# zero_board.net
KiCad netlist of a schematic drawn in EAGLE
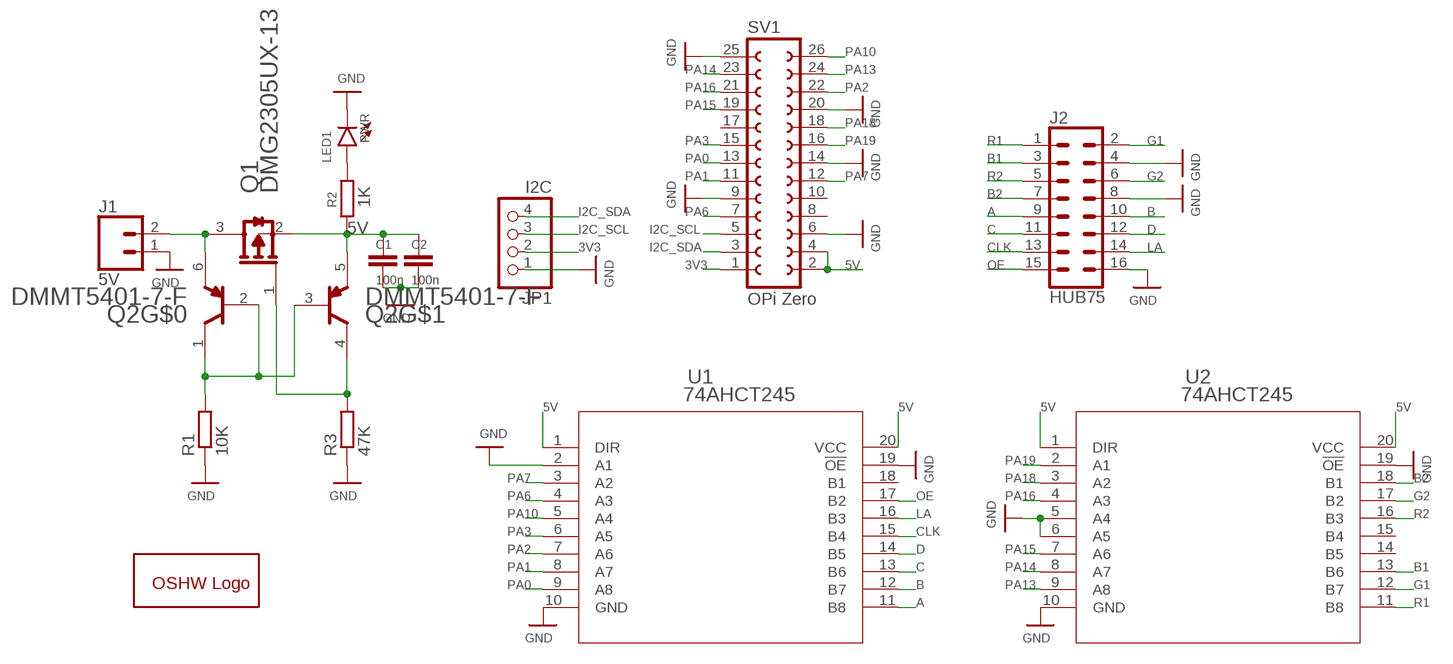
[diagram p0: schematic, sheet 1]

(export (version "E")
  (design (tool "Eeschema 10.0.6"))
  (components
    (comp (ref "C1")
      (value "100n")
      (footprint "eagle-import:C0603")
      (libsource (lib "eagle-import") (part "C-EUC0603"))
    )
    (comp (ref "C2")
      (value "100n")
      (footprint "eagle-import:C0603")
      (libsource (lib "eagle-import") (part "C-EUC0603"))
    )
    (comp (ref "GOLD_ORB_SM1")
      (value "OSHWLOGOLOGO5MM")
      (footprint "eagle-import:OSHW_5MM")
      (libsource (lib "eagle-import") (part "OSHWLOGOLOGO5MM"))
    )
    (comp (ref "J1")
      (value "5V")
      (footprint "eagle-import:SCREWTERMINAL-3.5MM-2")
      (libsource (lib "eagle-import") (part "CONN_023.5MM"))
    )
    (comp (ref "J2")
      (value "HUB75")
      (footprint "eagle-import:2X8-SHROUDED_LOCK")
      (libsource (lib "eagle-import") (part "CONN_08X2_SHROUD"))
    )
    (comp (ref "JP1")
      (value "I2C")
      (footprint "eagle-import:1X04")
      (libsource (lib "eagle-import") (part "PINHD-1X4"))
    )
    (comp (ref "LED1")
      (value "PWR")
      (footprint "eagle-import:CHIP-LED0603")
      (libsource (lib "eagle-import") (part "LEDCHIP-LED0603"))
    )
    (comp (ref "Q1")
      (value "DIODES_INC._DMG2305UX-13DIODES_INC._DMG2305UX-13_0_0")
      (footprint "eagle-import:DIODES_INC._DMG2305UX-13_0")
      (fields
        (field (name "DIGIKEY_PART_NUMBER") "DMG2305UX-13DICT-ND")
        (field (name "MF") "Diodes Inc.")
        (field (name "MOUSER_PART_NUMBER") "621-DMG2305UX-13")
      )
      (libsource (lib "eagle-import") (part "DIODES_INC._DMG2305UX-13DIODES_INC._DMG2305UX-13_0_0"))
    )
    (comp (ref "Q2")
      (value "DIODES_DMMT5401-7-FDIODES_DMMT5401-7-F_0_0")
      (footprint "eagle-import:DIODES_DMMT5401-7-F_0")
      (fields
        (field (name "DIGIKEY_PART_NUMBER") "DMMT5401-FDICT-ND")
        (field (name "MF") "Diodes")
        (field (name "MOUSER_PART_NUMBER") "621-DMMT5401-7-F")
      )
      (libsource (lib "eagle-import") (part "DIODES_DMMT5401-7-FDIODES_DMMT5401-7-F_0_0"))
    )
    (comp (ref "R1")
      (value "10K")
      (footprint "eagle-import:R0402")
      (libsource (lib "eagle-import") (part "R-EU_R0402"))
    )
    (comp (ref "R2")
      (value "1K")
      (footprint "eagle-import:R0603")
      (libsource (lib "eagle-import") (part "resistor_348_R-EU_R0603"))
    )
    (comp (ref "R3")
      (value "47K")
      (footprint "eagle-import:R0402")
      (libsource (lib "eagle-import") (part "R-EU_R0402"))
    )
    (comp (ref "SV1")
      (value "OPi Zero")
      (footprint "eagle-import:FE13-2")
      (libsource (lib "eagle-import") (part "FE13-2"))
    )
    (comp (ref "U1")
      (value "74AHCT245")
      (footprint "eagle-import:PW20")
      (fields
        (field (name "GENERIC_PART_NUMBER") "SN74HCT245")
        (field (name "MANUFACTURER") "Texas Instruments")
        (field (name "MANUFACTURER_PART_NUMBER") "SN74HCT245PWR")
      )
      (libsource (lib "eagle-import") (part "SN74HCT245PWR"))
    )
    (comp (ref "U2")
      (value "74AHCT245")
      (footprint "eagle-import:PW20")
      (fields
        (field (name "GENERIC_PART_NUMBER") "SN74HCT245")
        (field (name "MANUFACTURER") "Texas Instruments")
        (field (name "MANUFACTURER_PART_NUMBER") "SN74HCT245PWR")
      )
      (libsource (lib "eagle-import") (part "SN74HCT245PWR"))
    )
  )
  (nets
    (net (code "1") (name "/3V3") (class "Default")
      (node (ref "JP1") (pin "2") (pinfunction "2_2") (pintype "passive"))
      (node (ref "SV1") (pin "1") (pinfunction "1_1") (pintype "passive"))
    )
    (net (code "2") (name "/5V") (class "Default")
      (node (ref "C1") (pin "1") (pinfunction "1_1") (pintype "passive"))
      (node (ref "C2") (pin "1") (pinfunction "1_1") (pintype "passive"))
      (node (ref "Q1") (pin "2") (pinfunction "S_2") (pintype "passive"))
      (node (ref "Q2") (pin "5") (pinfunction "E2_5") (pintype "passive"))
      (node (ref "R2") (pin "1") (pinfunction "1_1") (pintype "passive"))
      (node (ref "SV1") (pin "2") (pinfunction "2_2") (pintype "passive"))
      (node (ref "SV1") (pin "4") (pinfunction "4_4") (pintype "passive"))
      (node (ref "U1") (pin "1") (pinfunction "DIR_1") (pintype "input"))
      (node (ref "U1") (pin "20") (pinfunction "VCC_20") (pintype "power_in"))
      (node (ref "U2") (pin "1") (pinfunction "DIR_1") (pintype "input"))
      (node (ref "U2") (pin "20") (pinfunction "VCC_20") (pintype "power_in"))
    )
    (net (code "3") (name "/A") (class "Default")
      (node (ref "J2") (pin "9") (pinfunction "9_9") (pintype "passive"))
      (node (ref "U1") (pin "11") (pinfunction "B8_11") (pintype "bidirectional"))
    )
    (net (code "4") (name "/B") (class "Default")
      (node (ref "J2") (pin "10") (pinfunction "10_10") (pintype "passive"))
      (node (ref "U1") (pin "12") (pinfunction "B7_12") (pintype "bidirectional"))
    )
    (net (code "5") (name "/B1") (class "Default")
      (node (ref "J2") (pin "3") (pinfunction "3_3") (pintype "passive"))
      (node (ref "U2") (pin "13") (pinfunction "B6_13") (pintype "bidirectional"))
    )
    (net (code "6") (name "/B2") (class "Default")
      (node (ref "J2") (pin "7") (pinfunction "7_7") (pintype "passive"))
      (node (ref "U2") (pin "18") (pinfunction "B1_18") (pintype "bidirectional"))
    )
    (net (code "7") (name "/C") (class "Default")
      (node (ref "J2") (pin "11") (pinfunction "11_11") (pintype "passive"))
      (node (ref "U1") (pin "13") (pinfunction "B6_13") (pintype "bidirectional"))
    )
    (net (code "8") (name "/CLK") (class "Default")
      (node (ref "J2") (pin "13") (pinfunction "13_13") (pintype "passive"))
      (node (ref "U1") (pin "15") (pinfunction "B4_15") (pintype "bidirectional"))
    )
    (net (code "9") (name "/D") (class "Default")
      (node (ref "J2") (pin "12") (pinfunction "12_12") (pintype "passive"))
      (node (ref "U1") (pin "14") (pinfunction "B5_14") (pintype "bidirectional"))
    )
    (net (code "10") (name "/G1") (class "Default")
      (node (ref "J2") (pin "2") (pinfunction "2_2") (pintype "passive"))
      (node (ref "U2") (pin "12") (pinfunction "B7_12") (pintype "bidirectional"))
    )
    (net (code "11") (name "/G2") (class "Default")
      (node (ref "J2") (pin "6") (pinfunction "6_6") (pintype "passive"))
      (node (ref "U2") (pin "17") (pinfunction "B2_17") (pintype "bidirectional"))
    )
    (net (code "12") (name "/I2C_SCL") (class "Default")
      (node (ref "JP1") (pin "3") (pinfunction "3_3") (pintype "passive"))
      (node (ref "SV1") (pin "5") (pinfunction "5_5") (pintype "passive"))
    )
    (net (code "13") (name "/I2C_SDA") (class "Default")
      (node (ref "JP1") (pin "4") (pinfunction "4_4") (pintype "passive"))
      (node (ref "SV1") (pin "3") (pinfunction "3_3") (pintype "passive"))
    )
    (net (code "14") (name "/LA") (class "Default")
      (node (ref "J2") (pin "14") (pinfunction "14_14") (pintype "passive"))
      (node (ref "U1") (pin "16") (pinfunction "B3_16") (pintype "bidirectional"))
    )
    (net (code "15") (name "/OE") (class "Default")
      (node (ref "J2") (pin "15") (pinfunction "15_15") (pintype "passive"))
      (node (ref "U1") (pin "17") (pinfunction "B2_17") (pintype "bidirectional"))
    )
    (net (code "16") (name "/PA0") (class "Default")
      (node (ref "SV1") (pin "13") (pinfunction "13_13") (pintype "passive"))
      (node (ref "U1") (pin "9") (pinfunction "A8_9") (pintype "bidirectional"))
    )
    (net (code "17") (name "/PA1") (class "Default")
      (node (ref "SV1") (pin "11") (pinfunction "11_11") (pintype "passive"))
      (node (ref "U1") (pin "8") (pinfunction "A7_8") (pintype "bidirectional"))
    )
    (net (code "18") (name "/PA2") (class "Default")
      (node (ref "SV1") (pin "22") (pinfunction "22_22") (pintype "passive"))
      (node (ref "U1") (pin "7") (pinfunction "A6_7") (pintype "bidirectional"))
    )
    (net (code "19") (name "/PA3") (class "Default")
      (node (ref "SV1") (pin "15") (pinfunction "15_15") (pintype "passive"))
      (node (ref "U1") (pin "6") (pinfunction "A5_6") (pintype "bidirectional"))
    )
    (net (code "20") (name "/PA6") (class "Default")
      (node (ref "SV1") (pin "7") (pinfunction "7_7") (pintype "passive"))
      (node (ref "U1") (pin "4") (pinfunction "A3_4") (pintype "bidirectional"))
    )
    (net (code "21") (name "/PA7") (class "Default")
      (node (ref "SV1") (pin "12") (pinfunction "12_12") (pintype "passive"))
      (node (ref "U1") (pin "3") (pinfunction "A2_3") (pintype "bidirectional"))
    )
    (net (code "22") (name "/PA10") (class "Default")
      (node (ref "SV1") (pin "26") (pinfunction "26_26") (pintype "passive"))
      (node (ref "U1") (pin "5") (pinfunction "A4_5") (pintype "bidirectional"))
    )
    (net (code "23") (name "/PA13") (class "Default")
      (node (ref "SV1") (pin "24") (pinfunction "24_24") (pintype "passive"))
      (node (ref "U2") (pin "9") (pinfunction "A8_9") (pintype "bidirectional"))
    )
    (net (code "24") (name "/PA14") (class "Default")
      (node (ref "SV1") (pin "23") (pinfunction "23_23") (pintype "passive"))
      (node (ref "U2") (pin "8") (pinfunction "A7_8") (pintype "bidirectional"))
    )
    (net (code "25") (name "/PA15") (class "Default")
      (node (ref "SV1") (pin "19") (pinfunction "19_19") (pintype "passive"))
      (node (ref "U2") (pin "7") (pinfunction "A6_7") (pintype "bidirectional"))
    )
    (net (code "26") (name "/PA16") (class "Default")
      (node (ref "SV1") (pin "21") (pinfunction "21_21") (pintype "passive"))
      (node (ref "U2") (pin "4") (pinfunction "A3_4") (pintype "bidirectional"))
    )
    (net (code "27") (name "/PA18") (class "Default")
      (node (ref "SV1") (pin "18") (pinfunction "18_18") (pintype "passive"))
      (node (ref "U2") (pin "3") (pinfunction "A2_3") (pintype "bidirectional"))
    )
    (net (code "28") (name "/PA19") (class "Default")
      (node (ref "SV1") (pin "16") (pinfunction "16_16") (pintype "passive"))
      (node (ref "U2") (pin "2") (pinfunction "A1_2") (pintype "bidirectional"))
    )
    (net (code "29") (name "/R1") (class "Default")
      (node (ref "J2") (pin "1") (pinfunction "1_1") (pintype "passive"))
      (node (ref "U2") (pin "11") (pinfunction "B8_11") (pintype "bidirectional"))
    )
    (net (code "30") (name "/R2") (class "Default")
      (node (ref "J2") (pin "5") (pinfunction "5_5") (pintype "passive"))
      (node (ref "U2") (pin "16") (pinfunction "B3_16") (pintype "bidirectional"))
    )
    (net (code "31") (name "GND") (class "Default")
      (node (ref "C1") (pin "2") (pinfunction "2_2") (pintype "passive"))
      (node (ref "C2") (pin "2") (pinfunction "2_2") (pintype "passive"))
      (node (ref "J1") (pin "1") (pinfunction "1_1") (pintype "passive"))
      (node (ref "J2") (pin "16") (pinfunction "16_16") (pintype "passive"))
      (node (ref "J2") (pin "4") (pinfunction "4_4") (pintype "passive"))
      (node (ref "J2") (pin "8") (pinfunction "8_8") (pintype "passive"))
      (node (ref "JP1") (pin "1") (pinfunction "1_1") (pintype "passive"))
      (node (ref "LED1") (pin "C") (pinfunction "C_C") (pintype "passive"))
      (node (ref "R1") (pin "1") (pinfunction "1_1") (pintype "passive"))
      (node (ref "R3") (pin "1") (pinfunction "1_1") (pintype "passive"))
      (node (ref "SV1") (pin "14") (pinfunction "14_14") (pintype "passive"))
      (node (ref "SV1") (pin "20") (pinfunction "20_20") (pintype "passive"))
      (node (ref "SV1") (pin "25") (pinfunction "25_25") (pintype "passive"))
      (node (ref "SV1") (pin "6") (pinfunction "6_6") (pintype "passive"))
      (node (ref "SV1") (pin "9") (pinfunction "9_9") (pintype "passive"))
      (node (ref "U1") (pin "10") (pinfunction "GND_10") (pintype "power_in"))
      (node (ref "U1") (pin "19") (pinfunction "~{OE}_19") (pintype "input"))
      (node (ref "U1") (pin "2") (pinfunction "A1_2") (pintype "bidirectional"))
      (node (ref "U2") (pin "10") (pinfunction "GND_10") (pintype "power_in"))
      (node (ref "U2") (pin "19") (pinfunction "~{OE}_19") (pintype "input"))
      (node (ref "U2") (pin "5") (pinfunction "A4_5") (pintype "bidirectional"))
      (node (ref "U2") (pin "6") (pinfunction "A5_6") (pintype "bidirectional"))
    )
    (net (code "32") (name "Net-(LED1-PadA)") (class "Default")
      (node (ref "LED1") (pin "A") (pinfunction "A_A") (pintype "passive"))
      (node (ref "R2") (pin "2") (pinfunction "2_2") (pintype "passive"))
    )
    (net (code "33") (name "Net-(Q1-D)") (class "Default")
      (node (ref "J1") (pin "2") (pinfunction "2_2") (pintype "passive"))
      (node (ref "Q1") (pin "3") (pinfunction "D_3") (pintype "passive"))
      (node (ref "Q2") (pin "6") (pinfunction "E1_6") (pintype "passive"))
    )
    (net (code "34") (name "Net-(Q1-G)") (class "Default")
      (node (ref "Q1") (pin "1") (pinfunction "G_1") (pintype "passive"))
      (node (ref "Q2") (pin "4") (pinfunction "C2_4") (pintype "passive"))
      (node (ref "R3") (pin "2") (pinfunction "2_2") (pintype "passive"))
    )
    (net (code "35") (name "Net-(Q2A-B1)") (class "Default")
      (node (ref "Q2") (pin "1") (pinfunction "C1_1") (pintype "passive"))
      (node (ref "Q2") (pin "2") (pinfunction "B1_2") (pintype "passive"))
      (node (ref "Q2") (pin "3") (pinfunction "B2_3") (pintype "passive"))
      (node (ref "R1") (pin "2") (pinfunction "2_2") (pintype "passive"))
    )
    (net (code "36") (name "unconnected-(SV1-Pad8)") (class "Default")
      (node (ref "SV1") (pin "8") (pinfunction "8_8") (pintype "passive"))
    )
    (net (code "37") (name "unconnected-(SV1-Pad10)") (class "Default")
      (node (ref "SV1") (pin "10") (pinfunction "10_10") (pintype "passive"))
    )
    (net (code "38") (name "unconnected-(SV1-Pad17)") (class "Default")
      (node (ref "SV1") (pin "17") (pinfunction "17_17") (pintype "passive"))
    )
    (net (code "39") (name "unconnected-(U1-B1-Pad18)") (class "Default")
      (node (ref "U1") (pin "18") (pinfunction "B1_18") (pintype "bidirectional"))
    )
    (net (code "40") (name "unconnected-(U2-B4-Pad15)") (class "Default")
      (node (ref "U2") (pin "15") (pinfunction "B4_15") (pintype "bidirectional"))
    )
    (net (code "41") (name "unconnected-(U2-B5-Pad14)") (class "Default")
      (node (ref "U2") (pin "14") (pinfunction "B5_14") (pintype "bidirectional"))
    )
  )
)
